# DFN-6_2x2.net
KiCad netlist of a schematic drawn in EAGLE
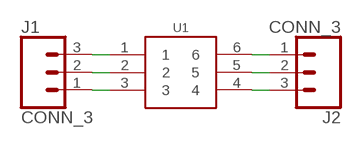
[diagram p0: schematic, sheet 1]

(export (version "E")
  (design (tool "Eeschema 10.0.6"))
  (components
    (comp (ref "J1")
      (value "CONN_3")
      (footprint "eagle-import:1X03")
      (libsource (lib "eagle-import") (part "CONN_3"))
    )
    (comp (ref "J2")
      (value "CONN_3")
      (footprint "eagle-import:1X03")
      (libsource (lib "eagle-import") (part "CONN_3"))
    )
    (comp (ref "U1")
      (value "GEN_6DFN_2X2")
      (footprint "eagle-import:DFN_6_2X2")
      (libsource (lib "eagle-import") (part "GEN_6DFN_2X2"))
    )
  )
  (nets
    (net (code "1") (name "Net-(J1-Pad1)") (class "Default")
      (node (ref "J1") (pin "1") (pinfunction "1_1") (pintype "passive"))
      (node (ref "U1") (pin "3") (pinfunction "3_3") (pintype "bidirectional"))
    )
    (net (code "2") (name "Net-(J1-Pad2)") (class "Default")
      (node (ref "J1") (pin "2") (pinfunction "2_2") (pintype "passive"))
      (node (ref "U1") (pin "2") (pinfunction "2_2") (pintype "bidirectional"))
    )
    (net (code "3") (name "Net-(J1-Pad3)") (class "Default")
      (node (ref "J1") (pin "3") (pinfunction "3_3") (pintype "passive"))
      (node (ref "U1") (pin "1") (pinfunction "1_1") (pintype "bidirectional"))
    )
    (net (code "4") (name "Net-(J2-Pad1)") (class "Default")
      (node (ref "J2") (pin "1") (pinfunction "1_1") (pintype "passive"))
      (node (ref "U1") (pin "6") (pinfunction "6_6") (pintype "bidirectional"))
    )
    (net (code "5") (name "Net-(J2-Pad2)") (class "Default")
      (node (ref "J2") (pin "2") (pinfunction "2_2") (pintype "passive"))
      (node (ref "U1") (pin "5") (pinfunction "5_5") (pintype "bidirectional"))
    )
    (net (code "6") (name "Net-(J2-Pad3)") (class "Default")
      (node (ref "J2") (pin "3") (pinfunction "3_3") (pintype "passive"))
      (node (ref "U1") (pin "4") (pinfunction "4_4") (pintype "bidirectional"))
    )
  )
)
